# ptn-piston_eagle7x.net
KiCad netlist of a schematic drawn in EAGLE
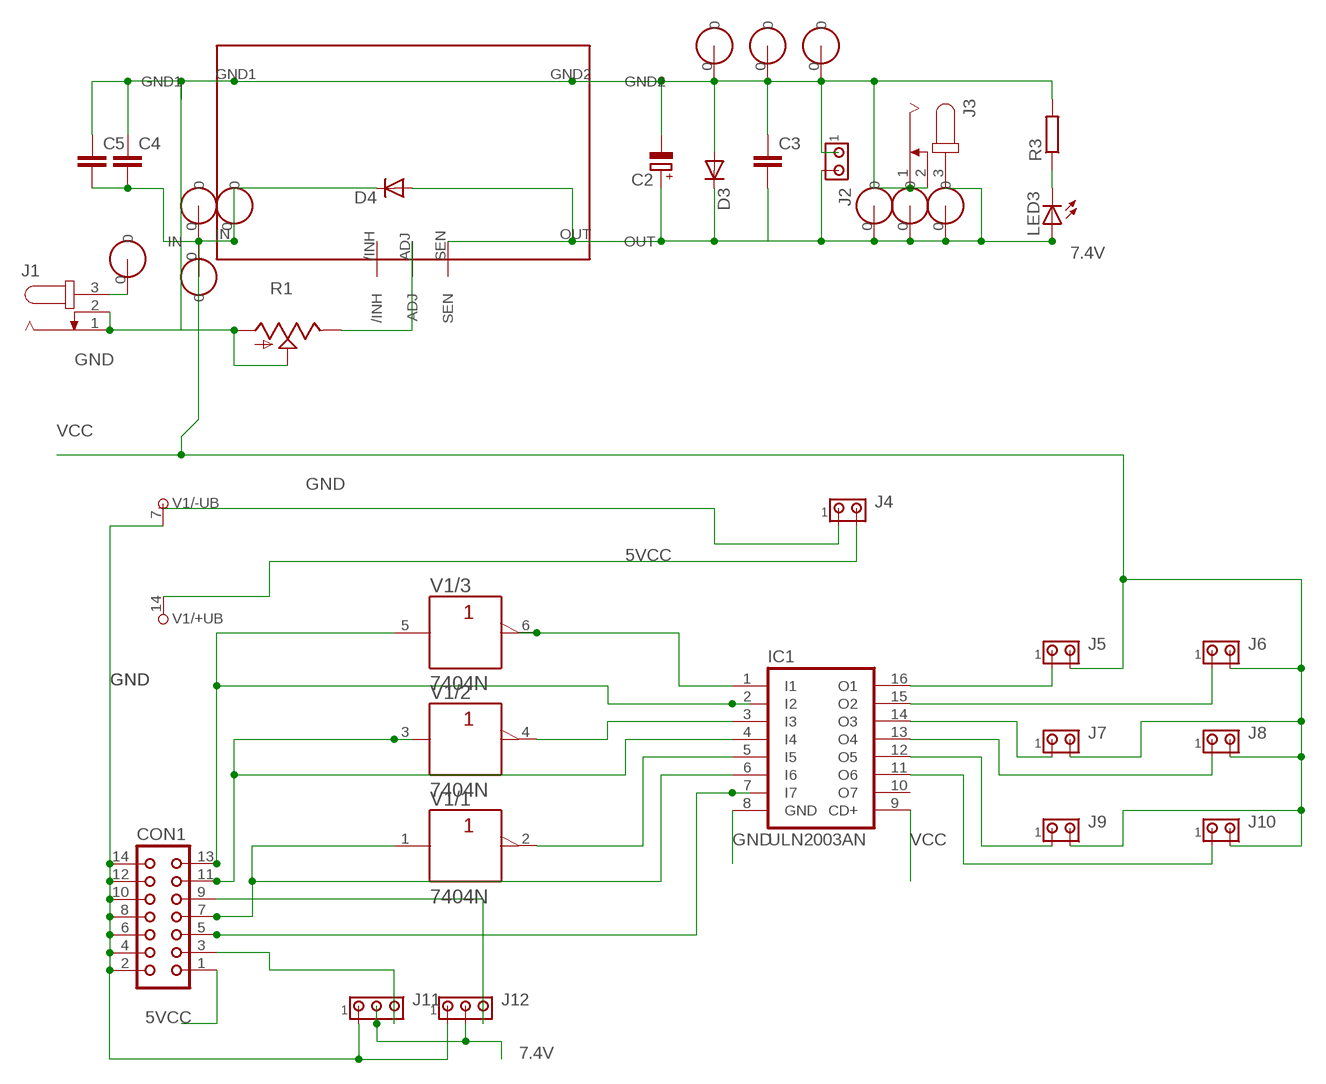
[diagram p0: schematic, sheet 1]

(export (version "E")
  (design (tool "Eeschema 10.0.6"))
  (components
    (comp (ref "C2")
      (value "CPOL-EUE3.5-8")
      (footprint "eagle-import:E3,5-8")
      (libsource (lib "eagle-import") (part "CPOL-EUE3.5-8"))
    )
    (comp (ref "C3")
      (value "C-EUC1206K")
      (footprint "eagle-import:C1206K")
      (libsource (lib "eagle-import") (part "C-EUC1206K"))
    )
    (comp (ref "C4")
      (value "C-EUC1206K")
      (footprint "eagle-import:C1206K")
      (libsource (lib "eagle-import") (part "C-EUC1206K"))
    )
    (comp (ref "C5")
      (value "C-EUC1206K")
      (footprint "eagle-import:C1206K")
      (libsource (lib "eagle-import") (part "C-EUC1206K"))
    )
    (comp (ref "CON1")
      (value "CON14")
      (footprint "eagle-import:CON14")
      (libsource (lib "eagle-import") (part "CON14"))
    )
    (comp (ref "D3")
      (value "DIODE-SMB")
      (footprint "eagle-import:SMB")
      (libsource (lib "eagle-import") (part "DIODE-SMB"))
    )
    (comp (ref "D4")
      (value "DIODE-SMB")
      (footprint "eagle-import:SMB")
      (libsource (lib "eagle-import") (part "DIODE-SMB"))
    )
    (comp (ref "IC1")
      (value "ULN2003AN")
      (footprint "eagle-import:DIL16")
      (libsource (lib "eagle-import") (part "ULN2003AN"))
    )
    (comp (ref "J1")
      (value "JACK-PLUG1")
      (footprint "eagle-import:SPC4078")
      (libsource (lib "eagle-import") (part "JACK-PLUG1"))
    )
    (comp (ref "J2")
      (value "MTA02-100")
      (footprint "eagle-import:10X02MTA")
      (libsource (lib "eagle-import") (part "MTA02-100"))
    )
    (comp (ref "J3")
      (value "JACK-PLUG1")
      (footprint "eagle-import:SPC4078")
      (libsource (lib "eagle-import") (part "JACK-PLUG1"))
    )
    (comp (ref "J4")
      (value "MTA02-100")
      (footprint "eagle-import:10X02MTA")
      (libsource (lib "eagle-import") (part "MTA02-100"))
    )
    (comp (ref "J5")
      (value "MTA02-100")
      (footprint "eagle-import:10X02MTA")
      (libsource (lib "eagle-import") (part "MTA02-100"))
    )
    (comp (ref "J6")
      (value "MTA02-100")
      (footprint "eagle-import:10X02MTA")
      (libsource (lib "eagle-import") (part "MTA02-100"))
    )
    (comp (ref "J7")
      (value "MTA02-100")
      (footprint "eagle-import:10X02MTA")
      (libsource (lib "eagle-import") (part "MTA02-100"))
    )
    (comp (ref "J8")
      (value "MTA02-100")
      (footprint "eagle-import:10X02MTA")
      (libsource (lib "eagle-import") (part "MTA02-100"))
    )
    (comp (ref "J9")
      (value "MTA02-100")
      (footprint "eagle-import:10X02MTA")
      (libsource (lib "eagle-import") (part "MTA02-100"))
    )
    (comp (ref "J10")
      (value "MTA02-100")
      (footprint "eagle-import:10X02MTA")
      (libsource (lib "eagle-import") (part "MTA02-100"))
    )
    (comp (ref "J11")
      (value "MTA03-100")
      (footprint "eagle-import:10X03MTA")
      (libsource (lib "eagle-import") (part "MTA03-100"))
    )
    (comp (ref "J12")
      (value "MTA03-100")
      (footprint "eagle-import:10X03MTA")
      (libsource (lib "eagle-import") (part "MTA03-100"))
    )
    (comp (ref "LED3")
      (value "LED3MM")
      (footprint "eagle-import:LED3MM")
      (libsource (lib "eagle-import") (part "LED3MM"))
    )
    (comp (ref "R1")
      (value "TRIM_US-B64Y")
      (footprint "eagle-import:B64Y")
      (libsource (lib "eagle-import") (part "TRIM_US-B64Y"))
    )
    (comp (ref "R3")
      (value "R-EU_R0603")
      (footprint "eagle-import:R0603")
      (libsource (lib "eagle-import") (part "R-EU_R0603"))
    )
    (comp (ref "U$1")
      (value "PTNPTN2")
      (footprint "eagle-import:PTN")
      (libsource (lib "eagle-import") (part "PTNPTN2"))
    )
    (comp (ref "U$2")
      (value "PAD0")
      (footprint "eagle-import:SWITCHPAD")
      (libsource (lib "eagle-import") (part "PAD0"))
    )
    (comp (ref "U$3")
      (value "PADSWITCHPAD1")
      (footprint "eagle-import:SWITCHPAD")
      (libsource (lib "eagle-import") (part "PADSWITCHPAD1"))
    )
    (comp (ref "U$4")
      (value "PADSWITCHPAD1")
      (footprint "eagle-import:SWITCHPAD")
      (libsource (lib "eagle-import") (part "PADSWITCHPAD1"))
    )
    (comp (ref "U$5")
      (value "PADSWITCHPAD1")
      (footprint "eagle-import:SWITCHPAD")
      (libsource (lib "eagle-import") (part "PADSWITCHPAD1"))
    )
    (comp (ref "U$6")
      (value "PADSWITCHPAD1")
      (footprint "eagle-import:SWITCHPAD")
      (libsource (lib "eagle-import") (part "PADSWITCHPAD1"))
    )
    (comp (ref "U$7")
      (value "PADSWITCHPAD1")
      (footprint "eagle-import:SWITCHPAD")
      (libsource (lib "eagle-import") (part "PADSWITCHPAD1"))
    )
    (comp (ref "U$8")
      (value "PADSWITCHPAD1")
      (footprint "eagle-import:SWITCHPAD")
      (libsource (lib "eagle-import") (part "PADSWITCHPAD1"))
    )
    (comp (ref "U$9")
      (value "PADSWITCHPAD1")
      (footprint "eagle-import:SWITCHPAD")
      (libsource (lib "eagle-import") (part "PADSWITCHPAD1"))
    )
    (comp (ref "U$10")
      (value "PADSWITCHPAD1")
      (footprint "eagle-import:SWITCHPAD")
      (libsource (lib "eagle-import") (part "PADSWITCHPAD1"))
    )
    (comp (ref "U$11")
      (value "PADSWITCHPAD1")
      (footprint "eagle-import:SWITCHPAD")
      (libsource (lib "eagle-import") (part "PADSWITCHPAD1"))
    )
    (comp (ref "V1")
      (value "7404N")
      (footprint "eagle-import:DIL14")
      (libsource (lib "eagle-import") (part "7404N"))
    )
  )
  (nets
    (net (code "1") (name "/5VCC") (class "Default")
      (node (ref "CON1") (pin "1") (pinfunction "1_1") (pintype "passive"))
      (node (ref "J4") (pin "2") (pinfunction "2_2") (pintype "passive"))
      (node (ref "V1") (pin "14") (pinfunction "+UB_14") (pintype "power_in"))
    )
    (net (code "2") (name "/7.4V") (class "Default")
      (node (ref "C2") (pin "+") (pinfunction "+_+") (pintype "passive"))
      (node (ref "C3") (pin "2") (pinfunction "2_2") (pintype "passive"))
      (node (ref "D3") (pin "C") (pinfunction "C_C") (pintype "passive"))
      (node (ref "D4") (pin "A") (pinfunction "A_A") (pintype "passive"))
      (node (ref "J11") (pin "2") (pinfunction "2_2") (pintype "passive"))
      (node (ref "J12") (pin "2") (pinfunction "2_2") (pintype "passive"))
      (node (ref "J2") (pin "2") (pinfunction "2_2") (pintype "passive"))
      (node (ref "J3") (pin "3") (pinfunction "3_3") (pintype "passive"))
      (node (ref "LED3") (pin "A") (pinfunction "A_A") (pintype "passive"))
      (node (ref "U$1") (pin "OUT") (pinfunction "OUT_OUT") (pintype "bidirectional"))
      (node (ref "U$1") (pin "SEN") (pinfunction "SEN_SEN") (pintype "bidirectional"))
      (node (ref "U$5") (pin "0") (pinfunction "0_0") (pintype "bidirectional"))
      (node (ref "U$7") (pin "0") (pinfunction "0_0") (pintype "bidirectional"))
      (node (ref "U$9") (pin "0") (pinfunction "0_0") (pintype "bidirectional"))
    )
    (net (code "3") (name "/GND") (class "Default")
      (node (ref "C2") (pin "-") (pinfunction "-_-") (pintype "passive"))
      (node (ref "C3") (pin "1") (pinfunction "1_1") (pintype "passive"))
      (node (ref "C4") (pin "1") (pinfunction "1_1") (pintype "passive"))
      (node (ref "C5") (pin "1") (pinfunction "1_1") (pintype "passive"))
      (node (ref "CON1") (pin "10") (pinfunction "10_10") (pintype "passive"))
      (node (ref "CON1") (pin "12") (pinfunction "12_12") (pintype "passive"))
      (node (ref "CON1") (pin "14") (pinfunction "14_14") (pintype "passive"))
      (node (ref "CON1") (pin "2") (pinfunction "2_2") (pintype "passive"))
      (node (ref "CON1") (pin "4") (pinfunction "4_4") (pintype "passive"))
      (node (ref "CON1") (pin "6") (pinfunction "6_6") (pintype "passive"))
      (node (ref "CON1") (pin "8") (pinfunction "8_8") (pintype "passive"))
      (node (ref "D3") (pin "A") (pinfunction "A_A") (pintype "passive"))
      (node (ref "IC1") (pin "8") (pinfunction "GND_8") (pintype "power_in"))
      (node (ref "J1") (pin "1") (pinfunction "1_1") (pintype "passive"))
      (node (ref "J1") (pin "2") (pinfunction "2_2") (pintype "passive"))
      (node (ref "J11") (pin "1") (pinfunction "1_1") (pintype "passive"))
      (node (ref "J12") (pin "1") (pinfunction "1_1") (pintype "passive"))
      (node (ref "J2") (pin "1") (pinfunction "1_1") (pintype "passive"))
      (node (ref "J3") (pin "1") (pinfunction "1_1") (pintype "passive"))
      (node (ref "J3") (pin "2") (pinfunction "2_2") (pintype "passive"))
      (node (ref "J4") (pin "1") (pinfunction "1_1") (pintype "passive"))
      (node (ref "R1") (pin "A") (pinfunction "A_A") (pintype "passive"))
      (node (ref "R1") (pin "S") (pinfunction "S_S") (pintype "passive"))
      (node (ref "R3") (pin "2") (pinfunction "2_2") (pintype "passive"))
      (node (ref "U$1") (pin "GND1") (pinfunction "GND1_GND1") (pintype "bidirectional"))
      (node (ref "U$1") (pin "GND2") (pinfunction "GND2_GND2") (pintype "bidirectional"))
      (node (ref "U$4") (pin "0") (pinfunction "0_0") (pintype "bidirectional"))
      (node (ref "U$6") (pin "0") (pinfunction "0_0") (pintype "bidirectional"))
      (node (ref "U$8") (pin "0") (pinfunction "0_0") (pintype "bidirectional"))
      (node (ref "V1") (pin "7") (pinfunction "-UB_7") (pintype "power_in"))
    )
    (net (code "4") (name "/VCC") (class "Default")
      (node (ref "C4") (pin "2") (pinfunction "2_2") (pintype "passive"))
      (node (ref "C5") (pin "2") (pinfunction "2_2") (pintype "passive"))
      (node (ref "D4") (pin "C") (pinfunction "C_C") (pintype "passive"))
      (node (ref "IC1") (pin "9") (pinfunction "CD+_9") (pintype "passive"))
      (node (ref "J10") (pin "2") (pinfunction "2_2") (pintype "passive"))
      (node (ref "J5") (pin "2") (pinfunction "2_2") (pintype "passive"))
      (node (ref "J6") (pin "2") (pinfunction "2_2") (pintype "passive"))
      (node (ref "J7") (pin "2") (pinfunction "2_2") (pintype "passive"))
      (node (ref "J8") (pin "2") (pinfunction "2_2") (pintype "passive"))
      (node (ref "J9") (pin "2") (pinfunction "2_2") (pintype "passive"))
      (node (ref "U$1") (pin "IN") (pinfunction "IN_IN") (pintype "bidirectional"))
      (node (ref "U$10") (pin "0") (pinfunction "0_0") (pintype "bidirectional"))
      (node (ref "U$11") (pin "0") (pinfunction "0_0") (pintype "bidirectional"))
      (node (ref "U$2") (pin "0") (pinfunction "0_0") (pintype "bidirectional"))
    )
    (net (code "5") (name "Net-(CON1-Pad3)") (class "Default")
      (node (ref "CON1") (pin "3") (pinfunction "3_3") (pintype "passive"))
      (node (ref "J11") (pin "3") (pinfunction "3_3") (pintype "passive"))
    )
    (net (code "6") (name "Net-(CON1-Pad9)") (class "Default")
      (node (ref "CON1") (pin "9") (pinfunction "9_9") (pintype "passive"))
      (node (ref "J12") (pin "3") (pinfunction "3_3") (pintype "passive"))
    )
    (net (code "7") (name "Net-(IC1-I1)") (class "Default")
      (node (ref "IC1") (pin "1") (pinfunction "I1_1") (pintype "input"))
      (node (ref "V1") (pin "6") (pinfunction "Y_6") (pintype "output"))
    )
    (net (code "8") (name "Net-(IC1-I2)") (class "Default")
      (node (ref "CON1") (pin "13") (pinfunction "13_13") (pintype "passive"))
      (node (ref "IC1") (pin "2") (pinfunction "I2_2") (pintype "input"))
      (node (ref "V1") (pin "5") (pinfunction "A_5") (pintype "input"))
    )
    (net (code "9") (name "Net-(IC1-I3)") (class "Default")
      (node (ref "IC1") (pin "3") (pinfunction "I3_3") (pintype "input"))
      (node (ref "V1") (pin "4") (pinfunction "Y_4") (pintype "output"))
    )
    (net (code "10") (name "Net-(IC1-I4)") (class "Default")
      (node (ref "CON1") (pin "11") (pinfunction "11_11") (pintype "passive"))
      (node (ref "IC1") (pin "4") (pinfunction "I4_4") (pintype "input"))
      (node (ref "V1") (pin "3") (pinfunction "A_3") (pintype "input"))
    )
    (net (code "11") (name "Net-(IC1-I5)") (class "Default")
      (node (ref "IC1") (pin "5") (pinfunction "I5_5") (pintype "input"))
      (node (ref "V1") (pin "2") (pinfunction "Y_2") (pintype "output"))
    )
    (net (code "12") (name "Net-(IC1-I6)") (class "Default")
      (node (ref "CON1") (pin "7") (pinfunction "7_7") (pintype "passive"))
      (node (ref "IC1") (pin "6") (pinfunction "I6_6") (pintype "input"))
      (node (ref "V1") (pin "1") (pinfunction "A_1") (pintype "input"))
    )
    (net (code "13") (name "Net-(IC1-I7)") (class "Default")
      (node (ref "CON1") (pin "5") (pinfunction "5_5") (pintype "passive"))
      (node (ref "IC1") (pin "7") (pinfunction "I7_7") (pintype "input"))
    )
    (net (code "14") (name "Net-(IC1-O1)") (class "Default")
      (node (ref "IC1") (pin "16") (pinfunction "O1_16") (pintype "open_collector"))
      (node (ref "J5") (pin "1") (pinfunction "1_1") (pintype "passive"))
    )
    (net (code "15") (name "Net-(IC1-O2)") (class "Default")
      (node (ref "IC1") (pin "15") (pinfunction "O2_15") (pintype "open_collector"))
      (node (ref "J6") (pin "1") (pinfunction "1_1") (pintype "passive"))
    )
    (net (code "16") (name "Net-(IC1-O3)") (class "Default")
      (node (ref "IC1") (pin "14") (pinfunction "O3_14") (pintype "open_collector"))
      (node (ref "J7") (pin "1") (pinfunction "1_1") (pintype "passive"))
    )
    (net (code "17") (name "Net-(IC1-O4)") (class "Default")
      (node (ref "IC1") (pin "13") (pinfunction "O4_13") (pintype "open_collector"))
      (node (ref "J8") (pin "1") (pinfunction "1_1") (pintype "passive"))
    )
    (net (code "18") (name "Net-(IC1-O5)") (class "Default")
      (node (ref "IC1") (pin "12") (pinfunction "O5_12") (pintype "open_collector"))
      (node (ref "J9") (pin "1") (pinfunction "1_1") (pintype "passive"))
    )
    (net (code "19") (name "Net-(IC1-O6)") (class "Default")
      (node (ref "IC1") (pin "11") (pinfunction "O6_11") (pintype "open_collector"))
      (node (ref "J10") (pin "1") (pinfunction "1_1") (pintype "passive"))
    )
    (net (code "20") (name "Net-(J1-Pad3)") (class "Default")
      (node (ref "J1") (pin "3") (pinfunction "3_3") (pintype "passive"))
      (node (ref "U$3") (pin "0") (pinfunction "0_0") (pintype "bidirectional"))
    )
    (net (code "21") (name "Net-(LED3-C)") (class "Default")
      (node (ref "LED3") (pin "K") (pinfunction "C_K") (pintype "passive"))
      (node (ref "R3") (pin "1") (pinfunction "1_1") (pintype "passive"))
    )
    (net (code "22") (name "Net-(R1-PadE)") (class "Default")
      (node (ref "R1") (pin "E") (pinfunction "E_E") (pintype "passive"))
      (node (ref "U$1") (pin "ADJ") (pinfunction "ADJ_ADJ") (pintype "bidirectional"))
    )
    (net (code "23") (name "unconnected-(IC1-O7-Pad10)") (class "Default")
      (node (ref "IC1") (pin "10") (pinfunction "O7_10") (pintype "open_collector"))
    )
    (net (code "24") (name "unconnected-(U$1-Pad{slash}INH)") (class "Default")
      (node (ref "U$1") (pin "/INH") (pinfunction "/INH_/INH") (pintype "bidirectional"))
    )
  )
)
